# Power_Supply2.net
KiCad netlist of a schematic drawn in Altium Designer
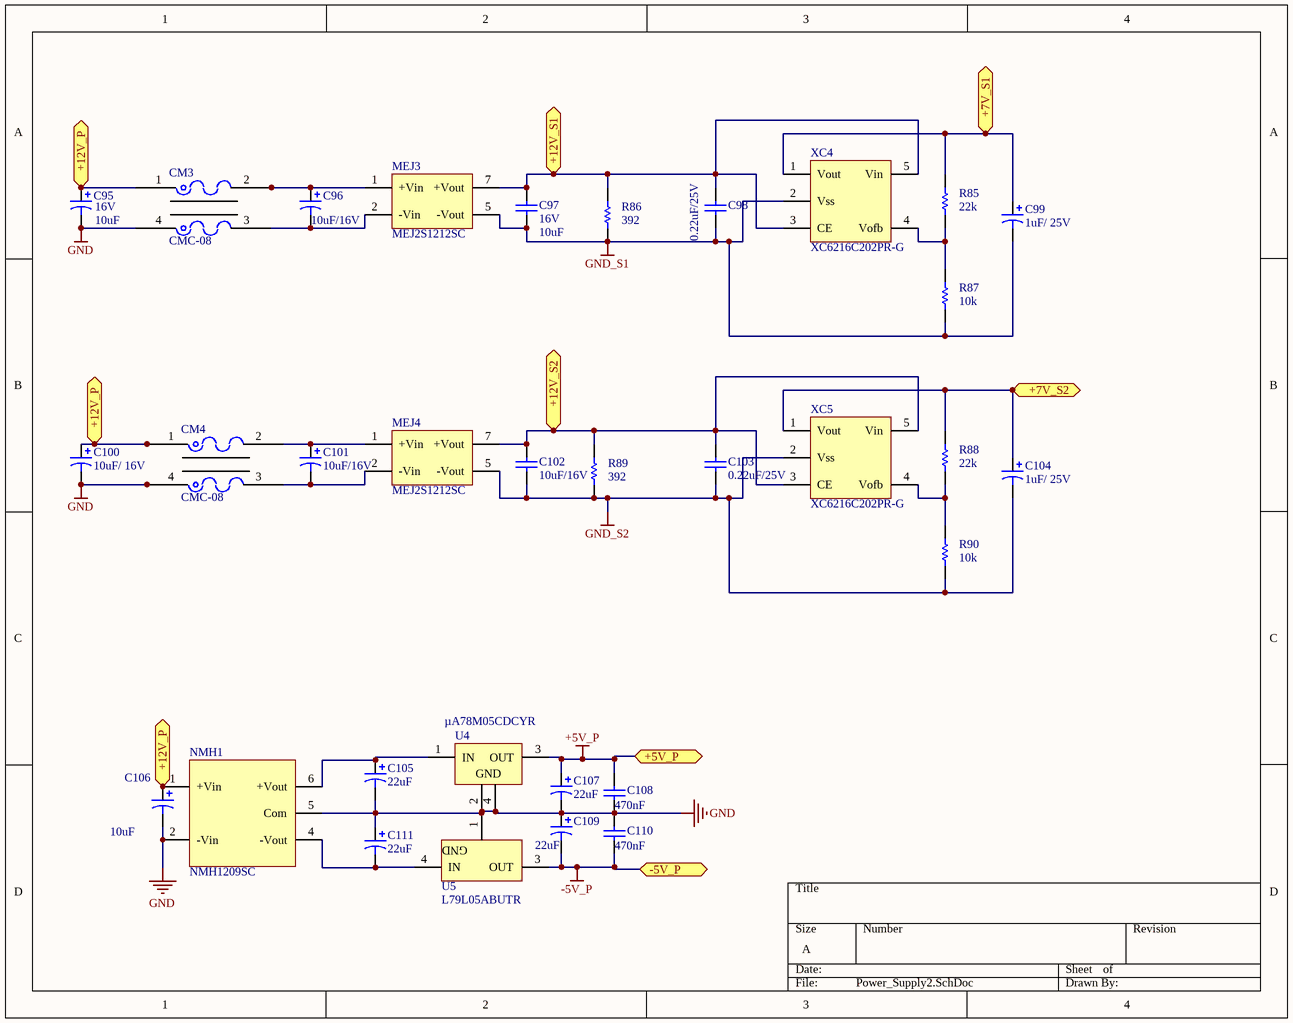
[diagram p0: Power_Supply2.SchDoc]

(export (version "E")
  (design (tool "Eeschema 10.0.6"))
  (components
    (comp (ref "C95")
      (value "16V")
      (footprint "1812")
      (description "Polarized Capacitor (Surface Mount)")
      (fields (field (name "ALTIUM_VALUE") "10uF") (field (name "PUBLISHER") "Altium Limited"))
      (libsource (lib "Miscellaneous Devices") (part "Cap Pol3"))
    )
    (comp (ref "C96")
      (value "10uF/16V")
      (footprint "1812")
      (description "Polarized Capacitor (Surface Mount)")
      (fields (field (name "Comment") "Cap Pol3") (field (name "PUBLISHER") "Altium Limited"))
      (libsource (lib "Miscellaneous Devices") (part "Cap Pol3"))
    )
    (comp (ref "C97")
      (value "16V")
      (footprint "C1206")
      (description "Capacitor (Semiconductor SIM Model)")
      (fields (field (name "ALTIUM_VALUE") "10uF") (field (name "PUBLISHER") "Altium Limited"))
      (libsource (lib "Miscellaneous Devices") (part "Cap Semi"))
    )
    (comp (ref "C98")
      (value "0.22uF/25V")
      (footprint "C1206")
      (description "Capacitor (Semiconductor SIM Model)")
      (fields (field (name "Comment") "Cap Semi") (field (name "PUBLISHER") "Altium Limited"))
      (libsource (lib "Miscellaneous Devices") (part "Cap Semi"))
    )
    (comp (ref "C99")
      (value "1uF/ 25V")
      (footprint "C0805")
      (description "Polarized Capacitor (Surface Mount)")
      (fields (field (name "Comment") "Cap Pol3") (field (name "PUBLISHER") "Altium Limited"))
      (libsource (lib "Miscellaneous Devices") (part "Cap Pol3"))
    )
    (comp (ref "C100")
      (value "10uF/ 16V")
      (footprint "1812")
      (description "Polarized Capacitor (Surface Mount)")
      (fields (field (name "Comment") "Cap Pol3") (field (name "PUBLISHER") "Altium Limited"))
      (libsource (lib "Miscellaneous Devices") (part "Cap Pol3"))
    )
    (comp (ref "C101")
      (value "10uF/16V")
      (footprint "1812")
      (description "Polarized Capacitor (Surface Mount)")
      (fields (field (name "Comment") "Cap Pol3") (field (name "PUBLISHER") "Altium Limited"))
      (libsource (lib "Miscellaneous Devices") (part "Cap Pol3"))
    )
    (comp (ref "C102")
      (value "10uF/16V")
      (footprint "C1206")
      (description "Capacitor (Semiconductor SIM Model)")
      (fields (field (name "Comment") "Cap Semi") (field (name "PUBLISHER") "Altium Limited"))
      (libsource (lib "Miscellaneous Devices") (part "Cap Semi"))
    )
    (comp (ref "C103")
      (value "0.22uF/25V")
      (footprint "C1206")
      (description "Capacitor (Semiconductor SIM Model)")
      (fields (field (name "Comment") "Cap Semi") (field (name "PUBLISHER") "Altium Limited"))
      (libsource (lib "Miscellaneous Devices") (part "Cap Semi"))
    )
    (comp (ref "C104")
      (value "1uF/ 25V")
      (footprint "C0805")
      (description "Polarized Capacitor (Surface Mount)")
      (fields (field (name "Comment") "Cap Pol3") (field (name "PUBLISHER") "Altium Limited"))
      (libsource (lib "Miscellaneous Devices") (part "Cap Pol3"))
    )
    (comp (ref "C105")
      (value "22uF")
      (footprint "Cap tantal 22u-25V")
      (description "Polarized Capacitor (Radial)")
      (fields (field (name "Comment") "Tantalium") (field (name "PUBLISHER") "Altium Limited"))
      (libsource (lib "Miscellaneous Devices") (part "Cap Pol1"))
    )
    (comp (ref "C106")
      (value "10uF")
      (footprint "CAP-10u-16V")
      (description "Polarized Capacitor (Radial)")
      (fields (field (name "Comment") "electrolytic") (field (name "PUBLISHER") "Altium Limited"))
      (libsource (lib "Miscellaneous Devices") (part "Cap Pol1"))
    )
    (comp (ref "C107")
      (value "22uF")
      (footprint "Cap Tantal 3216")
      (description "Polarized Capacitor (Radial)")
      (fields
        (field (name "Comment") "Tantalium/T520A226M006ATE090")
        (field (name "PUBLISHER") "Altium Limited")
      )
      (libsource (lib "Miscellaneous Devices") (part "Cap Pol1"))
    )
    (comp (ref "C108")
      (value "470nF")
      (footprint "Capacitor 0805")
      (description "Capacitor")
      (fields (field (name "Comment") "Cap") (field (name "PUBLISHER") "Altium Limited"))
      (libsource (lib "Miscellaneous Devices") (part "Cap"))
    )
    (comp (ref "C109")
      (value "22uF")
      (footprint "Cap Tantal 3216")
      (description "Polarized Capacitor (Radial)")
      (fields
        (field (name "Comment") "Tantalium/T520A226M006ATE090")
        (field (name "PUBLISHER") "Altium Limited")
      )
      (libsource (lib "Miscellaneous Devices") (part "Cap Pol1"))
    )
    (comp (ref "C110")
      (value "470nF")
      (footprint "Capacitor 0805")
      (description "Capacitor")
      (fields (field (name "Comment") "Cap") (field (name "PUBLISHER") "Altium Limited"))
      (libsource (lib "Miscellaneous Devices") (part "Cap"))
    )
    (comp (ref "C111")
      (value "22uF")
      (footprint "Cap tantal 22u-25V")
      (description "Polarized Capacitor (Radial)")
      (fields (field (name "Comment") "Tantalium") (field (name "PUBLISHER") "Altium Limited"))
      (libsource (lib "Miscellaneous Devices") (part "Cap Pol1"))
    )
    (comp (ref "CM3")
      (value "CMC-08")
      (footprint "CMC-08")
      (description "Common mode choke")
      (libsource (lib "lib_ankit") (part "CMC-08"))
    )
    (comp (ref "CM4")
      (value "CMC-08")
      (footprint "CMC-08")
      (description "Common mode choke")
      (libsource (lib "lib_ankit") (part "CMC-08"))
    )
    (comp (ref "MEJ3")
      (value "MEJ2S1212SC")
      (footprint "MEJ2")
      (libsource (lib "Gan_cuk converter") (part "Power supply2"))
    )
    (comp (ref "MEJ4")
      (value "MEJ2S1212SC")
      (footprint "MEJ2")
      (libsource (lib "Gan_cuk converter") (part "Power supply2"))
    )
    (comp (ref "NMH1")
      (value "NMH1209SC")
      (footprint "NMH1209SC")
      (libsource (lib "control Board") (part "NMH----SC_1"))
    )
    (comp (ref "R85")
      (value "res_smd")
      (footprint "res_smd")
      (description "smd_res")
      (fields (field (name "ALTIUM_UNNAMED_1") "22k"))
      (libsource (lib "Schlib1") (part "res_smd"))
    )
    (comp (ref "R86")
      (value "res_smd")
      (footprint "res_smd")
      (description "smd_res")
      (fields (field (name "ALTIUM_UNNAMED_1") "392"))
      (libsource (lib "Schlib1") (part "res_smd"))
    )
    (comp (ref "R87")
      (value "res_smd")
      (footprint "res_smd")
      (description "smd_res")
      (fields (field (name "ALTIUM_UNNAMED_1") "10k"))
      (libsource (lib "Schlib1") (part "res_smd"))
    )
    (comp (ref "R88")
      (value "res_smd")
      (footprint "res_smd")
      (description "smd_res")
      (fields (field (name "ALTIUM_UNNAMED_1") "22k"))
      (libsource (lib "Schlib1") (part "res_smd"))
    )
    (comp (ref "R89")
      (value "res_smd")
      (footprint "res_smd")
      (description "smd_res")
      (fields (field (name "ALTIUM_UNNAMED_1") "392"))
      (libsource (lib "Schlib1") (part "res_smd"))
    )
    (comp (ref "R90")
      (value "res_smd")
      (footprint "res_smd")
      (description "smd_res")
      (fields (field (name "ALTIUM_UNNAMED_1") "10k"))
      (libsource (lib "Schlib1") (part "res_smd"))
    )
    (comp (ref "U4")
      (value "µA78M05CDCYR")
      (footprint "Reg - SOT223")
      (description "Positive-Voltage Regulator")
      (fields (field (name "PUBLISHER") "Altium Limited"))
      (libsource (lib "control Board") (part "µA7805CKTER"))
    )
    (comp (ref "U5")
      (value "L79L05ABUTR")
      (footprint "Reg SOT-89")
      (description "Negative-Voltage Regulator")
      (fields (field (name "PUBLISHER") "Altium Limited"))
      (libsource (lib "TI Power Mgt Voltage Regulator") (part "µA79M05CKTPR"))
    )
    (comp (ref "XC4")
      (value "XC6216C202PR-G")
      (footprint "SOT-89-5")
      (libsource (lib "Gan_cuk converter") (part "power supply"))
    )
    (comp (ref "XC5")
      (value "XC6216C202PR-G")
      (footprint "SOT-89-5")
      (libsource (lib "Gan_cuk converter") (part "power supply"))
    )
  )
  (nets
    (net (code "1") (name "+5V_P") (class "Default")
      (node (ref "C107") (pin "1") (pinfunction "1_1") (pintype "passive"))
      (node (ref "C108") (pin "2") (pinfunction "2_2") (pintype "passive"))
      (node (ref "U4") (pin "3") (pinfunction "OUT_3") (pintype "power_in"))
    )
    (net (code "2") (name "-5V_P") (class "Default")
      (node (ref "C109") (pin "2") (pinfunction "2_2") (pintype "passive"))
      (node (ref "C110") (pin "1") (pinfunction "1_1") (pintype "passive"))
      (node (ref "U5") (pin "3") (pinfunction "OUT_3") (pintype "power_in"))
    )
    (net (code "3") (name "/+7V_S1") (class "Default")
      (node (ref "C99") (pin "1") (pinfunction "1_1") (pintype "passive"))
      (node (ref "R85") (pin "1") (pintype "passive"))
      (node (ref "XC4") (pin "1") (pinfunction "Vout_1") (pintype "passive"))
    )
    (net (code "4") (name "/+7V_S2") (class "Default")
      (node (ref "C104") (pin "1") (pinfunction "1_1") (pintype "passive"))
      (node (ref "R88") (pin "1") (pintype "passive"))
      (node (ref "XC5") (pin "1") (pinfunction "Vout_1") (pintype "passive"))
    )
    (net (code "5") (name "/+12V_P") (class "Default")
      (node (ref "C100") (pin "1") (pinfunction "1_1") (pintype "passive"))
      (node (ref "C106") (pin "1") (pinfunction "1_1") (pintype "passive"))
      (node (ref "C95") (pin "1") (pinfunction "1_1") (pintype "passive"))
      (node (ref "CM3") (pin "1") (pinfunction "1_1") (pintype "passive"))
      (node (ref "CM4") (pin "1") (pinfunction "1_1") (pintype "passive"))
      (node (ref "NMH1") (pin "1") (pinfunction "+Vin_1") (pintype "passive"))
    )
    (net (code "6") (name "/+12V_S1") (class "Default")
      (node (ref "C97") (pin "2") (pinfunction "2_2") (pintype "passive"))
      (node (ref "C98") (pin "2") (pinfunction "2_2") (pintype "passive"))
      (node (ref "MEJ3") (pin "7") (pinfunction "+Vout_7") (pintype "passive"))
      (node (ref "R86") (pin "1") (pintype "passive"))
      (node (ref "XC4") (pin "3") (pinfunction "CE_3") (pintype "passive"))
      (node (ref "XC4") (pin "5") (pinfunction "Vin_5") (pintype "passive"))
    )
    (net (code "7") (name "/+12V_S2") (class "Default")
      (node (ref "C102") (pin "2") (pinfunction "2_2") (pintype "passive"))
      (node (ref "C103") (pin "2") (pinfunction "2_2") (pintype "passive"))
      (node (ref "MEJ4") (pin "7") (pinfunction "+Vout_7") (pintype "passive"))
      (node (ref "R89") (pin "1") (pintype "passive"))
      (node (ref "XC5") (pin "3") (pinfunction "CE_3") (pintype "passive"))
      (node (ref "XC5") (pin "5") (pinfunction "Vin_5") (pintype "passive"))
    )
    (net (code "8") (name "GND") (class "Default")
      (node (ref "C100") (pin "2") (pinfunction "2_2") (pintype "passive"))
      (node (ref "C105") (pin "2") (pinfunction "2_2") (pintype "passive"))
      (node (ref "C106") (pin "2") (pinfunction "2_2") (pintype "passive"))
      (node (ref "C107") (pin "2") (pinfunction "2_2") (pintype "passive"))
      (node (ref "C108") (pin "1") (pinfunction "1_1") (pintype "passive"))
      (node (ref "C109") (pin "1") (pinfunction "1_1") (pintype "passive"))
      (node (ref "C110") (pin "2") (pinfunction "2_2") (pintype "passive"))
      (node (ref "C111") (pin "1") (pinfunction "1_1") (pintype "passive"))
      (node (ref "C95") (pin "2") (pinfunction "2_2") (pintype "passive"))
      (node (ref "CM3") (pin "4") (pinfunction "4_4") (pintype "passive"))
      (node (ref "CM4") (pin "4") (pinfunction "4_4") (pintype "passive"))
      (node (ref "NMH1") (pin "2") (pinfunction "-Vin_2") (pintype "passive"))
      (node (ref "NMH1") (pin "5") (pinfunction "Com_5") (pintype "passive"))
      (node (ref "U4") (pin "2") (pinfunction "GND_2") (pintype "power_in"))
      (node (ref "U4") (pin "4") (pinfunction "GND_4") (pintype "power_in"))
      (node (ref "U5") (pin "1") (pinfunction "GND_1") (pintype "power_in"))
    )
    (net (code "9") (name "GND_S1") (class "Default")
      (node (ref "C97") (pin "1") (pinfunction "1_1") (pintype "passive"))
      (node (ref "C98") (pin "1") (pinfunction "1_1") (pintype "passive"))
      (node (ref "C99") (pin "2") (pinfunction "2_2") (pintype "passive"))
      (node (ref "MEJ3") (pin "5") (pinfunction "-Vout_5") (pintype "passive"))
      (node (ref "R86") (pin "2") (pintype "passive"))
      (node (ref "R87") (pin "2") (pintype "passive"))
      (node (ref "XC4") (pin "2") (pinfunction "Vss_2") (pintype "passive"))
    )
    (net (code "10") (name "GND_S2") (class "Default")
      (node (ref "C102") (pin "1") (pinfunction "1_1") (pintype "passive"))
      (node (ref "C103") (pin "1") (pinfunction "1_1") (pintype "passive"))
      (node (ref "C104") (pin "2") (pinfunction "2_2") (pintype "passive"))
      (node (ref "MEJ4") (pin "5") (pinfunction "-Vout_5") (pintype "passive"))
      (node (ref "R89") (pin "2") (pintype "passive"))
      (node (ref "R90") (pin "2") (pintype "passive"))
      (node (ref "XC5") (pin "2") (pinfunction "Vss_2") (pintype "passive"))
    )
    (net (code "11") (name "Net-(MEJ3-+Vin)") (class "Default")
      (node (ref "C96") (pin "1") (pinfunction "1_1") (pintype "passive"))
      (node (ref "CM3") (pin "2") (pinfunction "2_2") (pintype "passive"))
      (node (ref "MEJ3") (pin "1") (pinfunction "+Vin_1") (pintype "passive"))
    )
    (net (code "12") (name "Net-(MEJ3--Vin)") (class "Default")
      (node (ref "C96") (pin "2") (pinfunction "2_2") (pintype "passive"))
      (node (ref "CM3") (pin "3") (pinfunction "3_3") (pintype "passive"))
      (node (ref "MEJ3") (pin "2") (pinfunction "-Vin_2") (pintype "passive"))
    )
    (net (code "13") (name "Net-(MEJ4-+Vin)") (class "Default")
      (node (ref "C101") (pin "1") (pinfunction "1_1") (pintype "passive"))
      (node (ref "CM4") (pin "2") (pinfunction "2_2") (pintype "passive"))
      (node (ref "MEJ4") (pin "1") (pinfunction "+Vin_1") (pintype "passive"))
    )
    (net (code "14") (name "Net-(MEJ4--Vin)") (class "Default")
      (node (ref "C101") (pin "2") (pinfunction "2_2") (pintype "passive"))
      (node (ref "CM4") (pin "3") (pinfunction "3_3") (pintype "passive"))
      (node (ref "MEJ4") (pin "2") (pinfunction "-Vin_2") (pintype "passive"))
    )
    (net (code "15") (name "Net-(NMH1-+Vout)") (class "Default")
      (node (ref "C105") (pin "1") (pinfunction "1_1") (pintype "passive"))
      (node (ref "NMH1") (pin "6") (pinfunction "+Vout_6") (pintype "passive"))
      (node (ref "U4") (pin "1") (pinfunction "IN_1") (pintype "power_in"))
    )
    (net (code "16") (name "Net-(NMH1--Vout)") (class "Default")
      (node (ref "C111") (pin "2") (pinfunction "2_2") (pintype "passive"))
      (node (ref "NMH1") (pin "4") (pinfunction "-Vout_4") (pintype "passive"))
      (node (ref "U5") (pin "4") (pinfunction "IN_4") (pintype "power_in"))
    )
    (net (code "17") (name "Net-(XC4-Vofb)") (class "Default")
      (node (ref "R85") (pin "2") (pintype "passive"))
      (node (ref "R87") (pin "1") (pintype "passive"))
      (node (ref "XC4") (pin "4") (pinfunction "Vofb_4") (pintype "passive"))
    )
    (net (code "18") (name "Net-(XC5-Vofb)") (class "Default")
      (node (ref "R88") (pin "2") (pintype "passive"))
      (node (ref "R90") (pin "1") (pintype "passive"))
      (node (ref "XC5") (pin "4") (pinfunction "Vofb_4") (pintype "passive"))
    )
  )
)
